# 7-SEGMENT_DISPLAY_4_DIGITS.net
KiCad netlist of a schematic drawn in Altium Designer
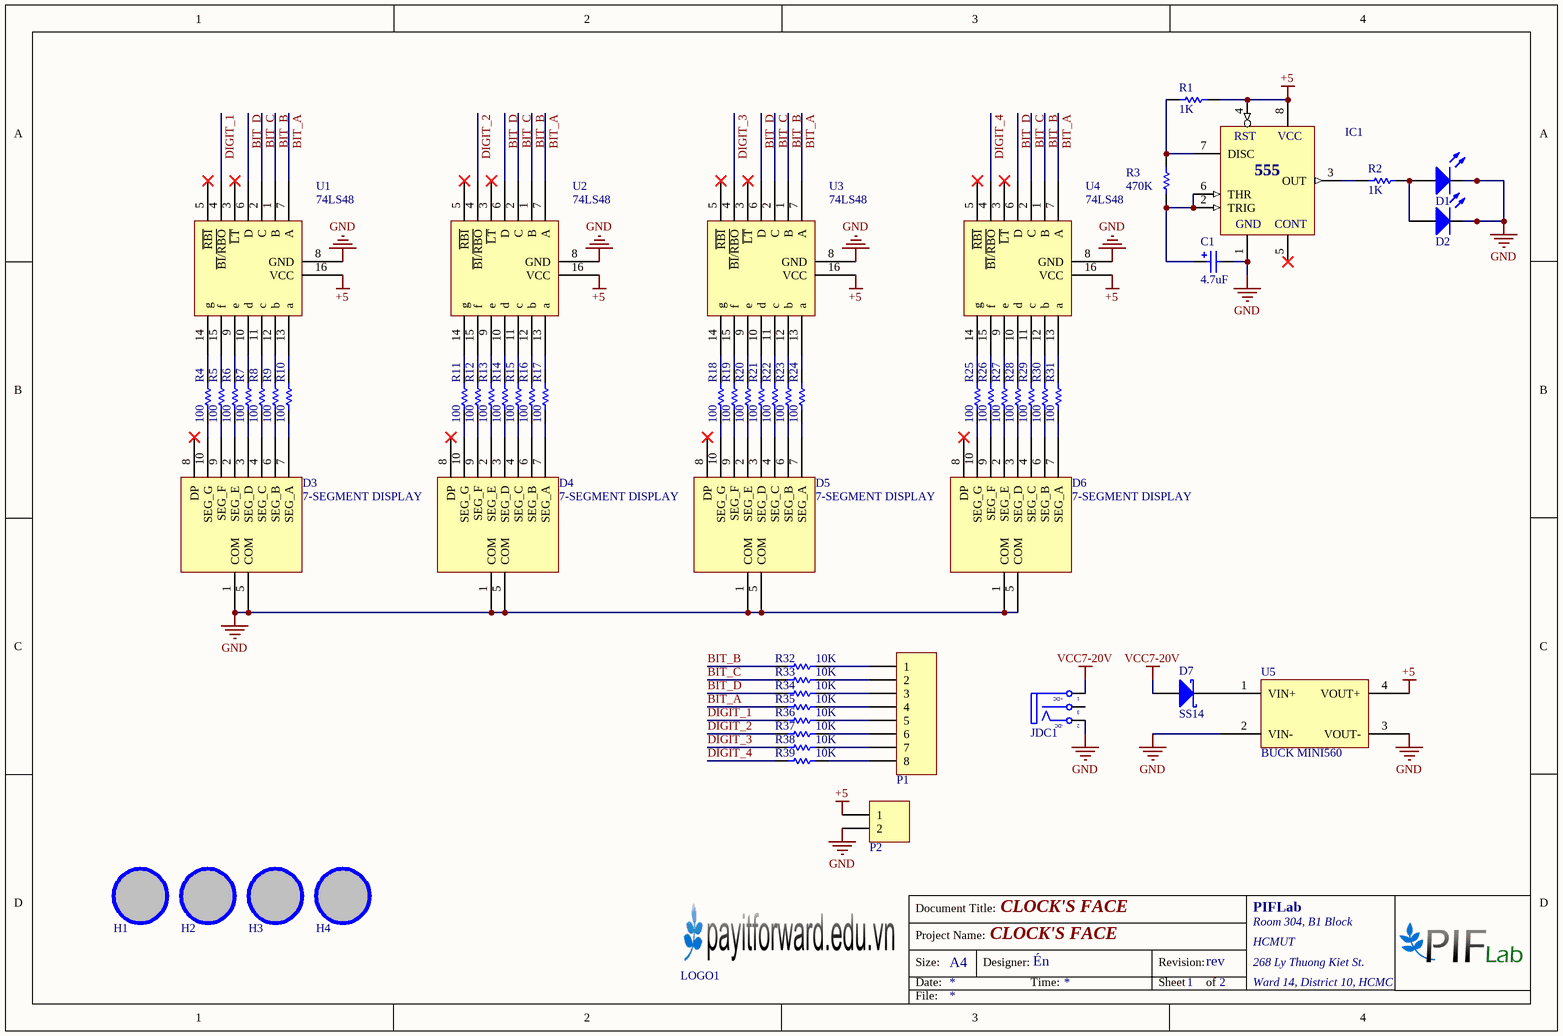
[diagram p0: 7-SEGMENT_DISPLAY_4_DIGITS.SchDoc]

(export (version "E")
  (design (tool "Eeschema 10.0.6"))
  (components
    (comp (ref "C1")
      (value "4.7uF")
      (footprint "CP1/2")
      (description "Polarized Capacitor (Radial)")
      (fields (field (name "Comment") "Cap Pol"))
      (libsource (lib "PIF_Library") (part "Cap Pol"))
    )
    (comp (ref "D1") (value "LED") (footprint "LED-3mm") (libsource (lib "PIF_Library") (part "LED")))
    (comp (ref "D2") (value "LED") (footprint "LED-3mm") (libsource (lib "PIF_Library") (part "LED")))
    (comp (ref "D3")
      (value "7-SEGMENT DISPLAY")
      (footprint "7-SEGMENT")
      (libsource (lib "Giang's Libs") (part "7-SEGMENT"))
    )
    (comp (ref "D4")
      (value "7-SEGMENT DISPLAY")
      (footprint "7-SEGMENT")
      (libsource (lib "Giang's Libs") (part "7-SEGMENT"))
    )
    (comp (ref "D5")
      (value "7-SEGMENT DISPLAY")
      (footprint "7-SEGMENT")
      (libsource (lib "Giang's Libs") (part "7-SEGMENT"))
    )
    (comp (ref "D6")
      (value "7-SEGMENT DISPLAY")
      (footprint "7-SEGMENT")
      (libsource (lib "Giang's Libs") (part "7-SEGMENT"))
    )
    (comp (ref "D7")
      (value "D Schottky")
      (footprint "SS34")
      (description "Schottky Diode")
      (fields (field (name "SUPPLIER PART NUMBER 1") "SS14") (field (name "PUBLISHER") "Altium Limited"))
      (libsource (lib "PIF_Library") (part "D Schottky"))
    )
    (comp (ref "H1")
      (value "Hole")
      (footprint "LO KHOAN 3MM")
      (description "Hole 3mm")
      (libsource (lib "PIF_Library") (part "Hole"))
    )
    (comp (ref "H2")
      (value "Hole")
      (footprint "LO KHOAN 3MM")
      (description "Hole 3mm")
      (libsource (lib "PIF_Library") (part "Hole"))
    )
    (comp (ref "H3")
      (value "Hole")
      (footprint "LO KHOAN 3MM")
      (description "Hole 3mm")
      (libsource (lib "PIF_Library") (part "Hole"))
    )
    (comp (ref "H4")
      (value "Hole")
      (footprint "LO KHOAN 3MM")
      (description "Hole 3mm")
      (libsource (lib "PIF_Library") (part "Hole"))
    )
    (comp (ref "IC1")
      (value "LM555")
      (footprint "DIP8/W0.3")
      (description "Timer")
      (libsource (lib "PIF_Library") (part "LM555"))
    )
    (comp (ref "JDC1")
      (value "Jack DC")
      (footprint "DC-IN")
      (description "Jack DC input")
      (libsource (lib "PIF_Library") (part "Jack DC"))
    )
    (comp (ref "LOGO1")
      (value "LOGO PIF")
      (footprint "PIF LOGO BIG TOP")
      (libsource (lib "PIF_Library") (part "LOGO PIF"))
    )
    (comp (ref "P1")
      (value "Header 8")
      (footprint "JP8")
      (description "Header, 8-Pin")
      (fields (field (name "PUBLISHER") "Altium Limited"))
      (libsource (lib "PIF_Library") (part "Header 8"))
    )
    (comp (ref "P2")
      (value "Header 2")
      (footprint "JP2")
      (description "Header, 2-Pin")
      (fields (field (name "PUBLISHER") "Altium Limited"))
      (libsource (lib "PIF_Library") (part "Header 2"))
    )
    (comp (ref "R1")
      (value "1K")
      (footprint "RES-SM-0805")
      (description "Resistor")
      (fields (field (name "Comment") "RESISTOR SMD"))
      (libsource (lib "PIF_Library") (part "RESISTOR SMD"))
    )
    (comp (ref "R2")
      (value "1K")
      (footprint "RES-SM-0805")
      (description "Resistor")
      (fields (field (name "Comment") "RESISTOR SMD"))
      (libsource (lib "PIF_Library") (part "RESISTOR SMD"))
    )
    (comp (ref "R3")
      (value "470K")
      (footprint "RES-SM-0805")
      (description "Resistor")
      (fields (field (name "Comment") "RESISTOR SMD"))
      (libsource (lib "PIF_Library") (part "RESISTOR SMD"))
    )
    (comp (ref "R4")
      (value "100")
      (footprint "RES-SM-0805")
      (description "Resistor")
      (fields (field (name "Comment") "RESISTOR SMD"))
      (libsource (lib "PIF_Library") (part "RESISTOR SMD"))
    )
    (comp (ref "R5")
      (value "100")
      (footprint "RES-SM-0805")
      (description "Resistor")
      (fields (field (name "Comment") "RESISTOR SMD"))
      (libsource (lib "PIF_Library") (part "RESISTOR SMD"))
    )
    (comp (ref "R6")
      (value "100")
      (footprint "RES-SM-0805")
      (description "Resistor")
      (fields (field (name "Comment") "RESISTOR SMD"))
      (libsource (lib "PIF_Library") (part "RESISTOR SMD"))
    )
    (comp (ref "R7")
      (value "100")
      (footprint "RES-SM-0805")
      (description "Resistor")
      (fields (field (name "Comment") "RESISTOR SMD"))
      (libsource (lib "PIF_Library") (part "RESISTOR SMD"))
    )
    (comp (ref "R8")
      (value "100")
      (footprint "RES-SM-0805")
      (description "Resistor")
      (fields (field (name "Comment") "RESISTOR SMD"))
      (libsource (lib "PIF_Library") (part "RESISTOR SMD"))
    )
    (comp (ref "R9")
      (value "100")
      (footprint "RES-SM-0805")
      (description "Resistor")
      (fields (field (name "Comment") "RESISTOR SMD"))
      (libsource (lib "PIF_Library") (part "RESISTOR SMD"))
    )
    (comp (ref "R10")
      (value "100")
      (footprint "RES-SM-0805")
      (description "Resistor")
      (fields (field (name "Comment") "RESISTOR SMD"))
      (libsource (lib "PIF_Library") (part "RESISTOR SMD"))
    )
    (comp (ref "R11")
      (value "100")
      (footprint "RES-SM-0805")
      (description "Resistor")
      (fields (field (name "Comment") "RESISTOR SMD"))
      (libsource (lib "PIF_Library") (part "RESISTOR SMD"))
    )
    (comp (ref "R12")
      (value "100")
      (footprint "RES-SM-0805")
      (description "Resistor")
      (fields (field (name "Comment") "RESISTOR SMD"))
      (libsource (lib "PIF_Library") (part "RESISTOR SMD"))
    )
    (comp (ref "R13")
      (value "100")
      (footprint "RES-SM-0805")
      (description "Resistor")
      (fields (field (name "Comment") "RESISTOR SMD"))
      (libsource (lib "PIF_Library") (part "RESISTOR SMD"))
    )
    (comp (ref "R14")
      (value "100")
      (footprint "RES-SM-0805")
      (description "Resistor")
      (fields (field (name "Comment") "RESISTOR SMD"))
      (libsource (lib "PIF_Library") (part "RESISTOR SMD"))
    )
    (comp (ref "R15")
      (value "100")
      (footprint "RES-SM-0805")
      (description "Resistor")
      (fields (field (name "Comment") "RESISTOR SMD"))
      (libsource (lib "PIF_Library") (part "RESISTOR SMD"))
    )
    (comp (ref "R16")
      (value "100")
      (footprint "RES-SM-0805")
      (description "Resistor")
      (fields (field (name "Comment") "RESISTOR SMD"))
      (libsource (lib "PIF_Library") (part "RESISTOR SMD"))
    )
    (comp (ref "R17")
      (value "100")
      (footprint "RES-SM-0805")
      (description "Resistor")
      (fields (field (name "Comment") "RESISTOR SMD"))
      (libsource (lib "PIF_Library") (part "RESISTOR SMD"))
    )
    (comp (ref "R18")
      (value "100")
      (footprint "RES-SM-0805")
      (description "Resistor")
      (fields (field (name "Comment") "RESISTOR SMD"))
      (libsource (lib "PIF_Library") (part "RESISTOR SMD"))
    )
    (comp (ref "R19")
      (value "100")
      (footprint "RES-SM-0805")
      (description "Resistor")
      (fields (field (name "Comment") "RESISTOR SMD"))
      (libsource (lib "PIF_Library") (part "RESISTOR SMD"))
    )
    (comp (ref "R20")
      (value "100")
      (footprint "RES-SM-0805")
      (description "Resistor")
      (fields (field (name "Comment") "RESISTOR SMD"))
      (libsource (lib "PIF_Library") (part "RESISTOR SMD"))
    )
    (comp (ref "R21")
      (value "100")
      (footprint "RES-SM-0805")
      (description "Resistor")
      (fields (field (name "Comment") "RESISTOR SMD"))
      (libsource (lib "PIF_Library") (part "RESISTOR SMD"))
    )
    (comp (ref "R22")
      (value "100")
      (footprint "RES-SM-0805")
      (description "Resistor")
      (fields (field (name "Comment") "RESISTOR SMD"))
      (libsource (lib "PIF_Library") (part "RESISTOR SMD"))
    )
    (comp (ref "R23")
      (value "100")
      (footprint "RES-SM-0805")
      (description "Resistor")
      (fields (field (name "Comment") "RESISTOR SMD"))
      (libsource (lib "PIF_Library") (part "RESISTOR SMD"))
    )
    (comp (ref "R24")
      (value "100")
      (footprint "RES-SM-0805")
      (description "Resistor")
      (fields (field (name "Comment") "RESISTOR SMD"))
      (libsource (lib "PIF_Library") (part "RESISTOR SMD"))
    )
    (comp (ref "R25")
      (value "100")
      (footprint "RES-SM-0805")
      (description "Resistor")
      (fields (field (name "Comment") "RESISTOR SMD"))
      (libsource (lib "PIF_Library") (part "RESISTOR SMD"))
    )
    (comp (ref "R26")
      (value "100")
      (footprint "RES-SM-0805")
      (description "Resistor")
      (fields (field (name "Comment") "RESISTOR SMD"))
      (libsource (lib "PIF_Library") (part "RESISTOR SMD"))
    )
    (comp (ref "R27")
      (value "100")
      (footprint "RES-SM-0805")
      (description "Resistor")
      (fields (field (name "Comment") "RESISTOR SMD"))
      (libsource (lib "PIF_Library") (part "RESISTOR SMD"))
    )
    (comp (ref "R28")
      (value "100")
      (footprint "RES-SM-0805")
      (description "Resistor")
      (fields (field (name "Comment") "RESISTOR SMD"))
      (libsource (lib "PIF_Library") (part "RESISTOR SMD"))
    )
    (comp (ref "R29")
      (value "100")
      (footprint "RES-SM-0805")
      (description "Resistor")
      (fields (field (name "Comment") "RESISTOR SMD"))
      (libsource (lib "PIF_Library") (part "RESISTOR SMD"))
    )
    (comp (ref "R30")
      (value "100")
      (footprint "RES-SM-0805")
      (description "Resistor")
      (fields (field (name "Comment") "RESISTOR SMD"))
      (libsource (lib "PIF_Library") (part "RESISTOR SMD"))
    )
    (comp (ref "R31")
      (value "100")
      (footprint "RES-SM-0805")
      (description "Resistor")
      (fields (field (name "Comment") "RESISTOR SMD"))
      (libsource (lib "PIF_Library") (part "RESISTOR SMD"))
    )
    (comp (ref "R32")
      (value "10K")
      (footprint "RES-SM-0805")
      (description "Resistor")
      (fields (field (name "Comment") "RESISTOR SMD"))
      (libsource (lib "PIF_Library") (part "RESISTOR SMD"))
    )
    (comp (ref "R33")
      (value "10K")
      (footprint "RES-SM-0805")
      (description "Resistor")
      (fields (field (name "Comment") "RESISTOR SMD"))
      (libsource (lib "PIF_Library") (part "RESISTOR SMD"))
    )
    (comp (ref "R34")
      (value "10K")
      (footprint "RES-SM-0805")
      (description "Resistor")
      (fields (field (name "Comment") "RESISTOR SMD"))
      (libsource (lib "PIF_Library") (part "RESISTOR SMD"))
    )
    (comp (ref "R35")
      (value "10K")
      (footprint "RES-SM-0805")
      (description "Resistor")
      (fields (field (name "Comment") "RESISTOR SMD"))
      (libsource (lib "PIF_Library") (part "RESISTOR SMD"))
    )
    (comp (ref "R36")
      (value "10K")
      (footprint "RES-SM-0805")
      (description "Resistor")
      (fields (field (name "Comment") "RESISTOR SMD"))
      (libsource (lib "PIF_Library") (part "RESISTOR SMD"))
    )
    (comp (ref "R37")
      (value "10K")
      (footprint "RES-SM-0805")
      (description "Resistor")
      (fields (field (name "Comment") "RESISTOR SMD"))
      (libsource (lib "PIF_Library") (part "RESISTOR SMD"))
    )
    (comp (ref "R38")
      (value "10K")
      (footprint "RES-SM-0805")
      (description "Resistor")
      (fields (field (name "Comment") "RESISTOR SMD"))
      (libsource (lib "PIF_Library") (part "RESISTOR SMD"))
    )
    (comp (ref "R39")
      (value "10K")
      (footprint "RES-SM-0805")
      (description "Resistor")
      (fields (field (name "Comment") "RESISTOR SMD"))
      (libsource (lib "PIF_Library") (part "RESISTOR SMD"))
    )
    (comp (ref "U1")
      (value "74LS48")
      (footprint "74LS48")
      (description "74LS48 - ACTIVE HIGH")
      (libsource (lib "Giang's Libs") (part "74LS48"))
    )
    (comp (ref "U2")
      (value "74LS48")
      (footprint "74LS48")
      (description "74LS48 - ACTIVE HIGH")
      (libsource (lib "Giang's Libs") (part "74LS48"))
    )
    (comp (ref "U3")
      (value "74LS48")
      (footprint "74LS48")
      (description "74LS48 - ACTIVE HIGH")
      (libsource (lib "Giang's Libs") (part "74LS48"))
    )
    (comp (ref "U4")
      (value "74LS48")
      (footprint "74LS48")
      (description "74LS48 - ACTIVE HIGH")
      (libsource (lib "Giang's Libs") (part "74LS48"))
    )
    (comp (ref "U5")
      (value "BUCK MINI560")
      (footprint "BUCK MINI560")
      (description "MODULE BUCK MINI560")
      (libsource (lib "Giang's Libs") (part "BUCK MINI560"))
    )
  )
  (nets
    (net (code "1") (name "+5") (class "Default")
      (node (ref "IC1") (pin "4") (pinfunction "RST_4") (pintype "input"))
      (node (ref "IC1") (pin "8") (pinfunction "VCC_8") (pintype "power_in"))
      (node (ref "P2") (pin "1") (pinfunction "1_1") (pintype "passive"))
      (node (ref "R1") (pin "2") (pinfunction "2_2") (pintype "passive"))
      (node (ref "U1") (pin "16") (pinfunction "VCC_16") (pintype "passive"))
      (node (ref "U2") (pin "16") (pinfunction "VCC_16") (pintype "passive"))
      (node (ref "U3") (pin "16") (pinfunction "VCC_16") (pintype "passive"))
      (node (ref "U4") (pin "16") (pinfunction "VCC_16") (pintype "passive"))
      (node (ref "U5") (pin "4") (pinfunction "VOUT+_4") (pintype "passive"))
    )
    (net (code "2") (name "/BIT_A") (class "Default")
      (node (ref "R35") (pin "1") (pinfunction "1_1") (pintype "passive"))
      (node (ref "U1") (pin "7") (pinfunction "A_7") (pintype "passive"))
      (node (ref "U2") (pin "7") (pinfunction "A_7") (pintype "passive"))
      (node (ref "U3") (pin "7") (pinfunction "A_7") (pintype "passive"))
      (node (ref "U4") (pin "7") (pinfunction "A_7") (pintype "passive"))
    )
    (net (code "3") (name "/BIT_B") (class "Default")
      (node (ref "R32") (pin "1") (pinfunction "1_1") (pintype "passive"))
      (node (ref "U1") (pin "1") (pinfunction "B_1") (pintype "passive"))
      (node (ref "U2") (pin "1") (pinfunction "B_1") (pintype "passive"))
      (node (ref "U3") (pin "1") (pinfunction "B_1") (pintype "passive"))
      (node (ref "U4") (pin "1") (pinfunction "B_1") (pintype "passive"))
    )
    (net (code "4") (name "/BIT_C") (class "Default")
      (node (ref "R33") (pin "1") (pinfunction "1_1") (pintype "passive"))
      (node (ref "U1") (pin "2") (pinfunction "C_2") (pintype "passive"))
      (node (ref "U2") (pin "2") (pinfunction "C_2") (pintype "passive"))
      (node (ref "U3") (pin "2") (pinfunction "C_2") (pintype "passive"))
      (node (ref "U4") (pin "2") (pinfunction "C_2") (pintype "passive"))
    )
    (net (code "5") (name "/BIT_D") (class "Default")
      (node (ref "R34") (pin "1") (pinfunction "1_1") (pintype "passive"))
      (node (ref "U1") (pin "6") (pinfunction "D_6") (pintype "passive"))
      (node (ref "U2") (pin "6") (pinfunction "D_6") (pintype "passive"))
      (node (ref "U3") (pin "6") (pinfunction "D_6") (pintype "passive"))
      (node (ref "U4") (pin "6") (pinfunction "D_6") (pintype "passive"))
    )
    (net (code "6") (name "/DIGIT_1") (class "Default")
      (node (ref "R36") (pin "1") (pinfunction "1_1") (pintype "passive"))
      (node (ref "U1") (pin "4") (pinfunction "~{BI}/~{RBO}_4") (pintype "passive"))
    )
    (net (code "7") (name "/DIGIT_2") (class "Default")
      (node (ref "R37") (pin "1") (pinfunction "1_1") (pintype "passive"))
      (node (ref "U2") (pin "4") (pinfunction "~{BI}/~{RBO}_4") (pintype "passive"))
    )
    (net (code "8") (name "/DIGIT_3") (class "Default")
      (node (ref "R38") (pin "1") (pinfunction "1_1") (pintype "passive"))
      (node (ref "U3") (pin "4") (pinfunction "~{BI}/~{RBO}_4") (pintype "passive"))
    )
    (net (code "9") (name "/DIGIT_4") (class "Default")
      (node (ref "R39") (pin "1") (pinfunction "1_1") (pintype "passive"))
      (node (ref "U4") (pin "4") (pinfunction "~{BI}/~{RBO}_4") (pintype "passive"))
    )
    (net (code "10") (name "GND") (class "Default")
      (node (ref "C1") (pin "2") (pinfunction "2_2") (pintype "passive"))
      (node (ref "D1") (pin "2") (pinfunction "K_2") (pintype "passive"))
      (node (ref "D2") (pin "2") (pinfunction "K_2") (pintype "passive"))
      (node (ref "D3") (pin "1") (pinfunction "COM_1") (pintype "passive"))
      (node (ref "D3") (pin "5") (pinfunction "COM_5") (pintype "passive"))
      (node (ref "D4") (pin "1") (pinfunction "COM_1") (pintype "passive"))
      (node (ref "D4") (pin "5") (pinfunction "COM_5") (pintype "passive"))
      (node (ref "D5") (pin "1") (pinfunction "COM_1") (pintype "passive"))
      (node (ref "D5") (pin "5") (pinfunction "COM_5") (pintype "passive"))
      (node (ref "D6") (pin "1") (pinfunction "COM_1") (pintype "passive"))
      (node (ref "D6") (pin "5") (pinfunction "COM_5") (pintype "passive"))
      (node (ref "IC1") (pin "1") (pinfunction "GND_1") (pintype "power_in"))
      (node (ref "JDC1") (pin "2") (pinfunction "TN_2") (pintype "passive"))
      (node (ref "P2") (pin "2") (pinfunction "2_2") (pintype "passive"))
      (node (ref "U1") (pin "8") (pinfunction "GND_8") (pintype "passive"))
      (node (ref "U2") (pin "8") (pinfunction "GND_8") (pintype "passive"))
      (node (ref "U3") (pin "8") (pinfunction "GND_8") (pintype "passive"))
      (node (ref "U4") (pin "8") (pinfunction "GND_8") (pintype "passive"))
      (node (ref "U5") (pin "2") (pinfunction "VIN-_2") (pintype "passive"))
      (node (ref "U5") (pin "3") (pinfunction "VOUT-_3") (pintype "passive"))
    )
    (net (code "11") (name "Net-(D1-A)") (class "Default")
      (node (ref "D1") (pin "1") (pinfunction "A_1") (pintype "passive"))
      (node (ref "D2") (pin "1") (pinfunction "A_1") (pintype "passive"))
      (node (ref "R2") (pin "2") (pinfunction "2_2") (pintype "passive"))
    )
    (net (code "12") (name "Net-(D3-SEG_A)") (class "Default")
      (node (ref "D3") (pin "7") (pinfunction "SEG_A_7") (pintype "passive"))
      (node (ref "R10") (pin "1") (pinfunction "1_1") (pintype "passive"))
    )
    (net (code "13") (name "Net-(D3-SEG_B)") (class "Default")
      (node (ref "D3") (pin "6") (pinfunction "SEG_B_6") (pintype "passive"))
      (node (ref "R9") (pin "1") (pinfunction "1_1") (pintype "passive"))
    )
    (net (code "14") (name "Net-(D3-SEG_C)") (class "Default")
      (node (ref "D3") (pin "4") (pinfunction "SEG_C_4") (pintype "passive"))
      (node (ref "R8") (pin "1") (pinfunction "1_1") (pintype "passive"))
    )
    (net (code "15") (name "Net-(D3-SEG_D)") (class "Default")
      (node (ref "D3") (pin "3") (pinfunction "SEG_D_3") (pintype "passive"))
      (node (ref "R7") (pin "1") (pinfunction "1_1") (pintype "passive"))
    )
    (net (code "16") (name "Net-(D3-SEG_E)") (class "Default")
      (node (ref "D3") (pin "2") (pinfunction "SEG_E_2") (pintype "passive"))
      (node (ref "R6") (pin "1") (pinfunction "1_1") (pintype "passive"))
    )
    (net (code "17") (name "Net-(D3-SEG_F)") (class "Default")
      (node (ref "D3") (pin "9") (pinfunction "SEG_F_9") (pintype "passive"))
      (node (ref "R5") (pin "1") (pinfunction "1_1") (pintype "passive"))
    )
    (net (code "18") (name "Net-(D3-SEG_G)") (class "Default")
      (node (ref "D3") (pin "10") (pinfunction "SEG_G_10") (pintype "passive"))
      (node (ref "R4") (pin "1") (pinfunction "1_1") (pintype "passive"))
    )
    (net (code "19") (name "Net-(D4-SEG_A)") (class "Default")
      (node (ref "D4") (pin "7") (pinfunction "SEG_A_7") (pintype "passive"))
      (node (ref "R17") (pin "1") (pinfunction "1_1") (pintype "passive"))
    )
    (net (code "20") (name "Net-(D4-SEG_B)") (class "Default")
      (node (ref "D4") (pin "6") (pinfunction "SEG_B_6") (pintype "passive"))
      (node (ref "R16") (pin "1") (pinfunction "1_1") (pintype "passive"))
    )
    (net (code "21") (name "Net-(D4-SEG_C)") (class "Default")
      (node (ref "D4") (pin "4") (pinfunction "SEG_C_4") (pintype "passive"))
      (node (ref "R15") (pin "1") (pinfunction "1_1") (pintype "passive"))
    )
    (net (code "22") (name "Net-(D4-SEG_D)") (class "Default")
      (node (ref "D4") (pin "3") (pinfunction "SEG_D_3") (pintype "passive"))
      (node (ref "R14") (pin "1") (pinfunction "1_1") (pintype "passive"))
    )
    (net (code "23") (name "Net-(D4-SEG_E)") (class "Default")
      (node (ref "D4") (pin "2") (pinfunction "SEG_E_2") (pintype "passive"))
      (node (ref "R13") (pin "1") (pinfunction "1_1") (pintype "passive"))
    )
    (net (code "24") (name "Net-(D4-SEG_F)") (class "Default")
      (node (ref "D4") (pin "9") (pinfunction "SEG_F_9") (pintype "passive"))
      (node (ref "R12") (pin "1") (pinfunction "1_1") (pintype "passive"))
    )
    (net (code "25") (name "Net-(D4-SEG_G)") (class "Default")
      (node (ref "D4") (pin "10") (pinfunction "SEG_G_10") (pintype "passive"))
      (node (ref "R11") (pin "1") (pinfunction "1_1") (pintype "passive"))
    )
    (net (code "26") (name "Net-(D5-SEG_A)") (class "Default")
      (node (ref "D5") (pin "7") (pinfunction "SEG_A_7") (pintype "passive"))
      (node (ref "R24") (pin "1") (pinfunction "1_1") (pintype "passive"))
    )
    (net (code "27") (name "Net-(D5-SEG_B)") (class "Default")
      (node (ref "D5") (pin "6") (pinfunction "SEG_B_6") (pintype "passive"))
      (node (ref "R23") (pin "1") (pinfunction "1_1") (pintype "passive"))
    )
    (net (code "28") (name "Net-(D5-SEG_C)") (class "Default")
      (node (ref "D5") (pin "4") (pinfunction "SEG_C_4") (pintype "passive"))
      (node (ref "R22") (pin "1") (pinfunction "1_1") (pintype "passive"))
    )
    (net (code "29") (name "Net-(D5-SEG_D)") (class "Default")
      (node (ref "D5") (pin "3") (pinfunction "SEG_D_3") (pintype "passive"))
      (node (ref "R21") (pin "1") (pinfunction "1_1") (pintype "passive"))
    )
    (net (code "30") (name "Net-(D5-SEG_E)") (class "Default")
      (node (ref "D5") (pin "2") (pinfunction "SEG_E_2") (pintype "passive"))
      (node (ref "R20") (pin "1") (pinfunction "1_1") (pintype "passive"))
    )
    (net (code "31") (name "Net-(D5-SEG_F)") (class "Default")
      (node (ref "D5") (pin "9") (pinfunction "SEG_F_9") (pintype "passive"))
      (node (ref "R19") (pin "1") (pinfunction "1_1") (pintype "passive"))
    )
    (net (code "32") (name "Net-(D5-SEG_G)") (class "Default")
      (node (ref "D5") (pin "10") (pinfunction "SEG_G_10") (pintype "passive"))
      (node (ref "R18") (pin "1") (pinfunction "1_1") (pintype "passive"))
    )
    (net (code "33") (name "Net-(D6-SEG_A)") (class "Default")
      (node (ref "D6") (pin "7") (pinfunction "SEG_A_7") (pintype "passive"))
      (node (ref "R31") (pin "1") (pinfunction "1_1") (pintype "passive"))
    )
    (net (code "34") (name "Net-(D6-SEG_B)") (class "Default")
      (node (ref "D6") (pin "6") (pinfunction "SEG_B_6") (pintype "passive"))
      (node (ref "R30") (pin "1") (pinfunction "1_1") (pintype "passive"))
    )
    (net (code "35") (name "Net-(D6-SEG_C)") (class "Default")
      (node (ref "D6") (pin "4") (pinfunction "SEG_C_4") (pintype "passive"))
      (node (ref "R29") (pin "1") (pinfunction "1_1") (pintype "passive"))
    )
    (net (code "36") (name "Net-(D6-SEG_D)") (class "Default")
      (node (ref "D6") (pin "3") (pinfunction "SEG_D_3") (pintype "passive"))
      (node (ref "R28") (pin "1") (pinfunction "1_1") (pintype "passive"))
    )
    (net (code "37") (name "Net-(D6-SEG_E)") (class "Default")
      (node (ref "D6") (pin "2") (pinfunction "SEG_E_2") (pintype "passive"))
      (node (ref "R27") (pin "1") (pinfunction "1_1") (pintype "passive"))
    )
    (net (code "38") (name "Net-(D6-SEG_F)") (class "Default")
      (node (ref "D6") (pin "9") (pinfunction "SEG_F_9") (pintype "passive"))
      (node (ref "R26") (pin "1") (pinfunction "1_1") (pintype "passive"))
    )
    (net (code "39") (name "Net-(D6-SEG_G)") (class "Default")
      (node (ref "D6") (pin "10") (pinfunction "SEG_G_10") (pintype "passive"))
      (node (ref "R25") (pin "1") (pinfunction "1_1") (pintype "passive"))
    )
    (net (code "40") (name "Net-(IC1-DISC)") (class "Default")
      (node (ref "IC1") (pin "7") (pinfunction "DISC_7") (pintype "open_collector"))
      (node (ref "R1") (pin "1") (pinfunction "1_1") (pintype "passive"))
      (node (ref "R3") (pin "2") (pinfunction "2_2") (pintype "passive"))
    )
    (net (code "41") (name "Net-(IC1-OUT)") (class "Default")
      (node (ref "IC1") (pin "3") (pinfunction "OUT_3") (pintype "output"))
      (node (ref "R2") (pin "1") (pinfunction "1_1") (pintype "passive"))
    )
    (net (code "42") (name "Net-(IC1-THR)") (class "Default")
      (node (ref "C1") (pin "1") (pinfunction "1_1") (pintype "passive"))
      (node (ref "IC1") (pin "2") (pinfunction "TRIG_2") (pintype "input"))
      (node (ref "IC1") (pin "6") (pinfunction "THR_6") (pintype "input"))
      (node (ref "R3") (pin "1") (pinfunction "1_1") (pintype "passive"))
    )
    (net (code "43") (name "Net-(P1-Pad1)") (class "Default")
      (node (ref "P1") (pin "1") (pinfunction "1_1") (pintype "passive"))
      (node (ref "R32") (pin "2") (pinfunction "2_2") (pintype "passive"))
    )
    (net (code "44") (name "Net-(P1-Pad2)") (class "Default")
      (node (ref "P1") (pin "2") (pinfunction "2_2") (pintype "passive"))
      (node (ref "R33") (pin "2") (pinfunction "2_2") (pintype "passive"))
    )
    (net (code "45") (name "Net-(P1-Pad3)") (class "Default")
      (node (ref "P1") (pin "3") (pinfunction "3_3") (pintype "passive"))
      (node (ref "R34") (pin "2") (pinfunction "2_2") (pintype "passive"))
    )
    (net (code "46") (name "Net-(P1-Pad4)") (class "Default")
      (node (ref "P1") (pin "4") (pinfunction "4_4") (pintype "passive"))
      (node (ref "R35") (pin "2") (pinfunction "2_2") (pintype "passive"))
    )
    (net (code "47") (name "Net-(P1-Pad5)") (class "Default")
      (node (ref "P1") (pin "5") (pinfunction "5_5") (pintype "passive"))
      (node (ref "R36") (pin "2") (pinfunction "2_2") (pintype "passive"))
    )
    (net (code "48") (name "Net-(P1-Pad6)") (class "Default")
      (node (ref "P1") (pin "6") (pinfunction "6_6") (pintype "passive"))
      (node (ref "R37") (pin "2") (pinfunction "2_2") (pintype "passive"))
    )
    (net (code "49") (name "Net-(P1-Pad7)") (class "Default")
      (node (ref "P1") (pin "7") (pinfunction "7_7") (pintype "passive"))
      (node (ref "R38") (pin "2") (pinfunction "2_2") (pintype "passive"))
    )
    (net (code "50") (name "Net-(P1-Pad8)") (class "Default")
      (node (ref "P1") (pin "8") (pinfunction "8_8") (pintype "passive"))
      (node (ref "R39") (pin "2") (pinfunction "2_2") (pintype "passive"))
    )
    (net (code "51") (name "Net-(U1-a)") (class "Default")
      (node (ref "R10") (pin "2") (pinfunction "2_2") (pintype "passive"))
      (node (ref "U1") (pin "13") (pinfunction "a_13") (pintype "passive"))
    )
    (net (code "52") (name "Net-(U1-b)") (class "Default")
      (node (ref "R9") (pin "2") (pinfunction "2_2") (pintype "passive"))
      (node (ref "U1") (pin "12") (pinfunction "b_12") (pintype "passive"))
    )
    (net (code "53") (name "Net-(U1-c)") (class "Default")
      (node (ref "R8") (pin "2") (pinfunction "2_2") (pintype "passive"))
      (node (ref "U1") (pin "11") (pinfunction "c_11") (pintype "passive"))
    )
    (net (code "54") (name "Net-(U1-d)") (class "Default")
      (node (ref "R7") (pin "2") (pinfunction "2_2") (pintype "passive"))
      (node (ref "U1") (pin "10") (pinfunction "d_10") (pintype "passive"))
    )
    (net (code "55") (name "Net-(U1-e)") (class "Default")
      (node (ref "R6") (pin "2") (pinfunction "2_2") (pintype "passive"))
      (node (ref "U1") (pin "9") (pinfunction "e_9") (pintype "passive"))
    )
    (net (code "56") (name "Net-(U1-f)") (class "Default")
      (node (ref "R5") (pin "2") (pinfunction "2_2") (pintype "passive"))
      (node (ref "U1") (pin "15") (pinfunction "f_15") (pintype "passive"))
    )
    (net (code "57") (name "Net-(U1-g)") (class "Default")
      (node (ref "R4") (pin "2") (pinfunction "2_2") (pintype "passive"))
      (node (ref "U1") (pin "14") (pinfunction "g_14") (pintype "passive"))
    )
    (net (code "58") (name "Net-(U2-a)") (class "Default")
      (node (ref "R17") (pin "2") (pinfunction "2_2") (pintype "passive"))
      (node (ref "U2") (pin "13") (pinfunction "a_13") (pintype "passive"))
    )
    (net (code "59") (name "Net-(U2-b)") (class "Default")
      (node (ref "R16") (pin "2") (pinfunction "2_2") (pintype "passive"))
      (node (ref "U2") (pin "12") (pinfunction "b_12") (pintype "passive"))
    )
    (net (code "60") (name "Net-(U2-c)") (class "Default")
      (node (ref "R15") (pin "2") (pinfunction "2_2") (pintype "passive"))
      (node (ref "U2") (pin "11") (pinfunction "c_11") (pintype "passive"))
    )
    (net (code "61") (name "Net-(U2-d)") (class "Default")
      (node (ref "R14") (pin "2") (pinfunction "2_2") (pintype "passive"))
      (node (ref "U2") (pin "10") (pinfunction "d_10") (pintype "passive"))
    )
    (net (code "62") (name "Net-(U2-e)") (class "Default")
      (node (ref "R13") (pin "2") (pinfunction "2_2") (pintype "passive"))
      (node (ref "U2") (pin "9") (pinfunction "e_9") (pintype "passive"))
    )
    (net (code "63") (name "Net-(U2-f)") (class "Default")
      (node (ref "R12") (pin "2") (pinfunction "2_2") (pintype "passive"))
      (node (ref "U2") (pin "15") (pinfunction "f_15") (pintype "passive"))
    )
    (net (code "64") (name "Net-(U2-g)") (class "Default")
      (node (ref "R11") (pin "2") (pinfunction "2_2") (pintype "passive"))
      (node (ref "U2") (pin "14") (pinfunction "g_14") (pintype "passive"))
    )
    (net (code "65") (name "Net-(U3-a)") (class "Default")
      (node (ref "R24") (pin "2") (pinfunction "2_2") (pintype "passive"))
      (node (ref "U3") (pin "13") (pinfunction "a_13") (pintype "passive"))
    )
    (net (code "66") (name "Net-(U3-b)") (class "Default")
      (node (ref "R23") (pin "2") (pinfunction "2_2") (pintype "passive"))
      (node (ref "U3") (pin "12") (pinfunction "b_12") (pintype "passive"))
    )
    (net (code "67") (name "Net-(U3-c)") (class "Default")
      (node (ref "R22") (pin "2") (pinfunction "2_2") (pintype "passive"))
      (node (ref "U3") (pin "11") (pinfunction "c_11") (pintype "passive"))
    )
    (net (code "68") (name "Net-(U3-d)") (class "Default")
      (node (ref "R21") (pin "2") (pinfunction "2_2") (pintype "passive"))
      (node (ref "U3") (pin "10") (pinfunction "d_10") (pintype "passive"))
    )
    (net (code "69") (name "Net-(U3-e)") (class "Default")
      (node (ref "R20") (pin "2") (pinfunction "2_2") (pintype "passive"))
      (node (ref "U3") (pin "9") (pinfunction "e_9") (pintype "passive"))
    )
    (net (code "70") (name "Net-(U3-f)") (class "Default")
      (node (ref "R19") (pin "2") (pinfunction "2_2") (pintype "passive"))
      (node (ref "U3") (pin "15") (pinfunction "f_15") (pintype "passive"))
    )
    (net (code "71") (name "Net-(U3-g)") (class "Default")
      (node (ref "R18") (pin "2") (pinfunction "2_2") (pintype "passive"))
      (node (ref "U3") (pin "14") (pinfunction "g_14") (pintype "passive"))
    )
    (net (code "72") (name "Net-(U4-a)") (class "Default")
      (node (ref "R31") (pin "2") (pinfunction "2_2") (pintype "passive"))
      (node (ref "U4") (pin "13") (pinfunction "a_13") (pintype "passive"))
    )
    (net (code "73") (name "Net-(U4-b)") (class "Default")
      (node (ref "R30") (pin "2") (pinfunction "2_2") (pintype "passive"))
      (node (ref "U4") (pin "12") (pinfunction "b_12") (pintype "passive"))
    )
    (net (code "74") (name "Net-(U4-c)") (class "Default")
      (node (ref "R29") (pin "2") (pinfunction "2_2") (pintype "passive"))
      (node (ref "U4") (pin "11") (pinfunction "c_11") (pintype "passive"))
    )
    (net (code "75") (name "Net-(U4-d)") (class "Default")
      (node (ref "R28") (pin "2") (pinfunction "2_2") (pintype "passive"))
      (node (ref "U4") (pin "10") (pinfunction "d_10") (pintype "passive"))
    )
    (net (code "76") (name "Net-(U4-e)") (class "Default")
      (node (ref "R27") (pin "2") (pinfunction "2_2") (pintype "passive"))
      (node (ref "U4") (pin "9") (pinfunction "e_9") (pintype "passive"))
    )
    (net (code "77") (name "Net-(U4-f)") (class "Default")
      (node (ref "R26") (pin "2") (pinfunction "2_2") (pintype "passive"))
      (node (ref "U4") (pin "15") (pinfunction "f_15") (pintype "passive"))
    )
    (net (code "78") (name "Net-(U4-g)") (class "Default")
      (node (ref "R25") (pin "2") (pinfunction "2_2") (pintype "passive"))
      (node (ref "U4") (pin "14") (pinfunction "g_14") (pintype "passive"))
    )
    (net (code "79") (name "Net-(U5-VIN+)") (class "Default")
      (node (ref "D7") (pin "K") (pinfunction "K_K") (pintype "passive"))
      (node (ref "U5") (pin "1") (pinfunction "VIN+_1") (pintype "passive"))
    )
    (net (code "80") (name "VCC7-20V") (class "Default")
      (node (ref "D7") (pin "A") (pinfunction "A_A") (pintype "passive"))
      (node (ref "JDC1") (pin "1") (pinfunction "T_1") (pintype "passive"))
    )
    (net (code "81") (name "unconnected-(D3-DP-Pad8)") (class "Default")
      (node (ref "D3") (pin "8") (pinfunction "DP_8") (pintype "passive+no_connect"))
    )
    (net (code "82") (name "unconnected-(D4-DP-Pad8)") (class "Default")
      (node (ref "D4") (pin "8") (pinfunction "DP_8") (pintype "passive+no_connect"))
    )
    (net (code "83") (name "unconnected-(D5-DP-Pad8)") (class "Default")
      (node (ref "D5") (pin "8") (pinfunction "DP_8") (pintype "passive+no_connect"))
    )
    (net (code "84") (name "unconnected-(D6-DP-Pad8)") (class "Default")
      (node (ref "D6") (pin "8") (pinfunction "DP_8") (pintype "passive+no_connect"))
    )
    (net (code "85") (name "unconnected-(H1-Pad1)") (class "Default")
      (node (ref "H1") (pin "1") (pinfunction "1_1") (pintype "passive"))
    )
    (net (code "86") (name "unconnected-(H2-Pad1)") (class "Default")
      (node (ref "H2") (pin "1") (pinfunction "1_1") (pintype "passive"))
    )
    (net (code "87") (name "unconnected-(H3-Pad1)") (class "Default")
      (node (ref "H3") (pin "1") (pinfunction "1_1") (pintype "passive"))
    )
    (net (code "88") (name "unconnected-(H4-Pad1)") (class "Default")
      (node (ref "H4") (pin "1") (pinfunction "1_1") (pintype "passive"))
    )
    (net (code "89") (name "unconnected-(IC1-CONT-Pad5)") (class "Default")
      (node (ref "IC1") (pin "5") (pinfunction "CONT_5") (pintype "passive+no_connect"))
    )
    (net (code "90") (name "unconnected-(JDC1-S-Pad3)") (class "Default")
      (node (ref "JDC1") (pin "3") (pinfunction "S_3") (pintype "power_in"))
    )
    (net (code "91") (name "unconnected-(U1-~{LT}-Pad3)") (class "Default")
      (node (ref "U1") (pin "3") (pinfunction "~{LT}_3") (pintype "passive+no_connect"))
    )
    (net (code "92") (name "unconnected-(U1-~{RBI}-Pad5)") (class "Default")
      (node (ref "U1") (pin "5") (pinfunction "~{RBI}_5") (pintype "passive+no_connect"))
    )
    (net (code "93") (name "unconnected-(U2-~{LT}-Pad3)") (class "Default")
      (node (ref "U2") (pin "3") (pinfunction "~{LT}_3") (pintype "passive+no_connect"))
    )
    (net (code "94") (name "unconnected-(U2-~{RBI}-Pad5)") (class "Default")
      (node (ref "U2") (pin "5") (pinfunction "~{RBI}_5") (pintype "passive+no_connect"))
    )
    (net (code "95") (name "unconnected-(U3-~{LT}-Pad3)") (class "Default")
      (node (ref "U3") (pin "3") (pinfunction "~{LT}_3") (pintype "passive+no_connect"))
    )
    (net (code "96") (name "unconnected-(U3-~{RBI}-Pad5)") (class "Default")
      (node (ref "U3") (pin "5") (pinfunction "~{RBI}_5") (pintype "passive+no_connect"))
    )
    (net (code "97") (name "unconnected-(U4-~{LT}-Pad3)") (class "Default")
      (node (ref "U4") (pin "3") (pinfunction "~{LT}_3") (pintype "passive+no_connect"))
    )
    (net (code "98") (name "unconnected-(U4-~{RBI}-Pad5)") (class "Default")
      (node (ref "U4") (pin "5") (pinfunction "~{RBI}_5") (pintype "passive+no_connect"))
    )
  )
)
